# encoder.net
KiCad netlist of a schematic drawn in EAGLE
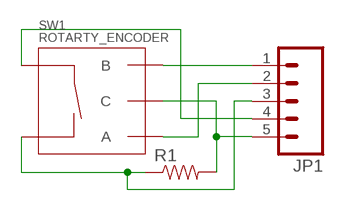
[diagram p0: schematic, sheet 1]

(export (version "E")
  (design (tool "Eeschema 10.0.6"))
  (components
    (comp (ref "JP1")
      (value "M05PTH")
      (footprint "eagle-import:1X05")
      (libsource (lib "eagle-import") (part "M05PTH"))
    )
    (comp (ref "R1")
      (value "RESISTORPTH-1/4W")
      (footprint "eagle-import:AXIAL-0.4")
      (libsource (lib "eagle-import") (part "RESISTORPTH-1/4W"))
    )
    (comp (ref "SW1")
      (value "ROTARTY_ENCODER")
      (footprint "eagle-import:ROTARY_ENC_PLAIN")
      (libsource (lib "eagle-import") (part "ROTARTY_ENCODER"))
    )
  )
  (nets
    (net (code "1") (name "Net-(JP1-Pad1)") (class "Default")
      (node (ref "JP1") (pin "1") (pinfunction "1_1") (pintype "passive"))
      (node (ref "SW1") (pin "B") (pinfunction "B_B") (pintype "bidirectional"))
    )
    (net (code "2") (name "Net-(JP1-Pad2)") (class "Default")
      (node (ref "JP1") (pin "2") (pinfunction "2_2") (pintype "passive"))
      (node (ref "SW1") (pin "A") (pinfunction "A_A") (pintype "bidirectional"))
    )
    (net (code "3") (name "Net-(JP1-Pad4)") (class "Default")
      (node (ref "JP1") (pin "4") (pinfunction "4_4") (pintype "passive"))
      (node (ref "SW1") (pin "SW+") (pinfunction "SW+_SW+") (pintype "bidirectional"))
    )
    (net (code "4") (name "Net-(R1-1)") (class "Default")
      (node (ref "JP1") (pin "3") (pinfunction "3_3") (pintype "passive"))
      (node (ref "R1") (pin "P$1") (pinfunction "1_P$1") (pintype "passive"))
      (node (ref "SW1") (pin "SW-") (pinfunction "SW-_SW-") (pintype "bidirectional"))
    )
    (net (code "5") (name "Net-(R1-2)") (class "Default")
      (node (ref "JP1") (pin "5") (pinfunction "5_5") (pintype "passive"))
      (node (ref "R1") (pin "P$2") (pinfunction "2_P$2") (pintype "passive"))
      (node (ref "SW1") (pin "C") (pinfunction "C_C") (pintype "bidirectional"))
    )
  )
)
